# Arduino2.net
KiCad netlist of a schematic drawn in EAGLE
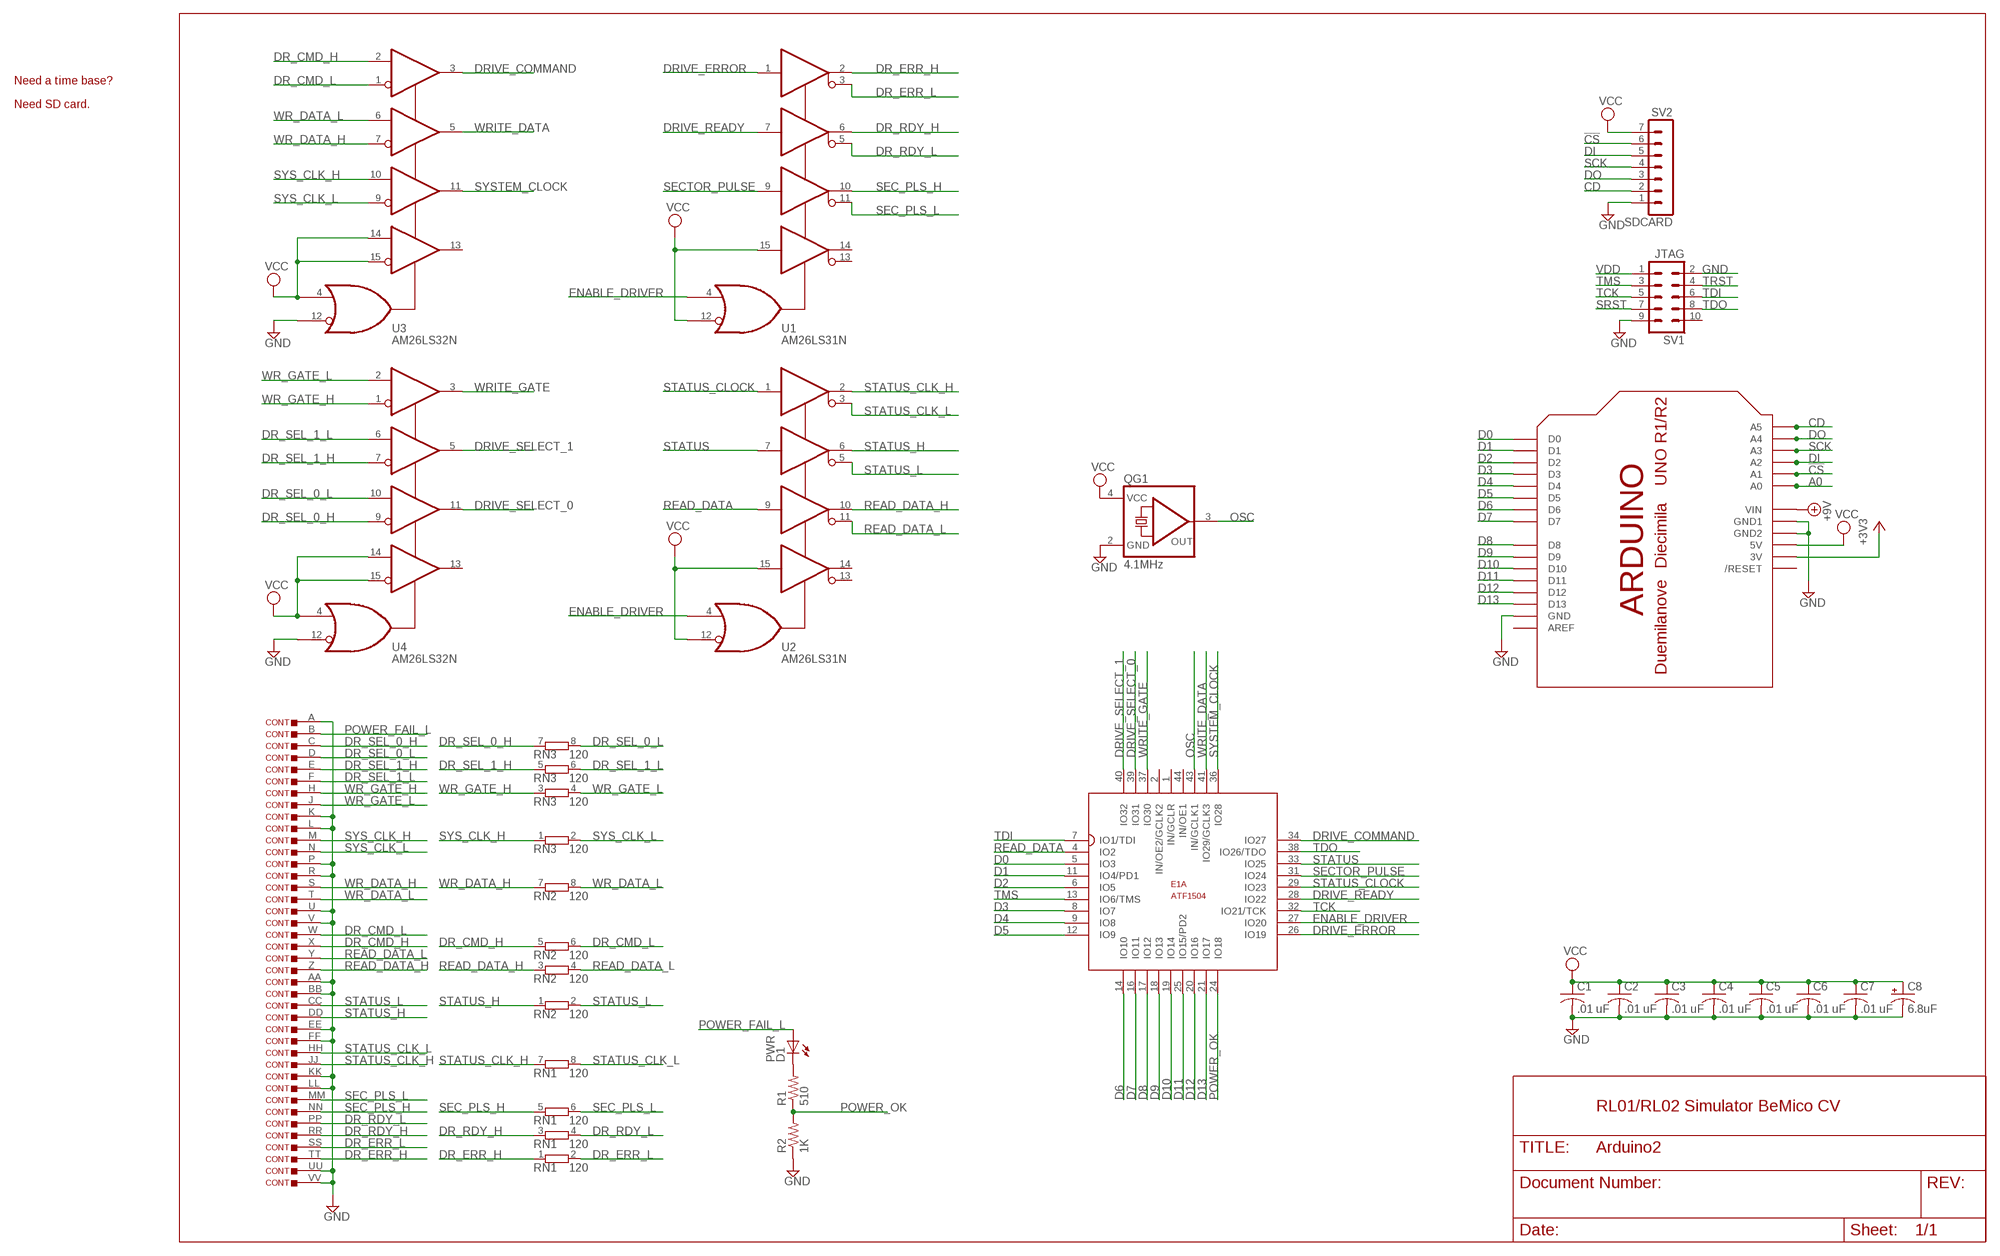
[diagram p0: schematic, sheet 1]

(export (version "E")
  (design (tool "Eeschema 10.0.6"))
  (components
    (comp (ref "C1")
      (value ".01 uF")
      (footprint "eagle-import:C050-025X075")
      (libsource (lib "eagle-import") (part "C-US050-025X075"))
    )
    (comp (ref "C2")
      (value ".01 uF")
      (footprint "eagle-import:C050-025X075")
      (libsource (lib "eagle-import") (part "C-US050-025X075"))
    )
    (comp (ref "C3")
      (value ".01 uF")
      (footprint "eagle-import:C050-025X075")
      (libsource (lib "eagle-import") (part "C-US050-025X075"))
    )
    (comp (ref "C4")
      (value ".01 uF")
      (footprint "eagle-import:C050-025X075")
      (libsource (lib "eagle-import") (part "C-US050-025X075"))
    )
    (comp (ref "C5")
      (value ".01 uF")
      (footprint "eagle-import:C050-025X075")
      (libsource (lib "eagle-import") (part "C-US050-025X075"))
    )
    (comp (ref "C6")
      (value ".01 uF")
      (footprint "eagle-import:C050-025X075")
      (libsource (lib "eagle-import") (part "C-US050-025X075"))
    )
    (comp (ref "C7")
      (value ".01 uF")
      (footprint "eagle-import:C050-025X075")
      (libsource (lib "eagle-import") (part "C-US050-025X075"))
    )
    (comp (ref "C8")
      (value "6.8uF")
      (footprint "eagle-import:E5-5")
      (libsource (lib "eagle-import") (part "CPOL-USE5-5"))
    )
    (comp (ref "CONT")
      (value "DEC40PINSV")
      (footprint "eagle-import:DEC40PINV")
      (libsource (lib "eagle-import") (part "DEC40PINSV"))
    )
    (comp (ref "D1")
      (value "PWR")
      (footprint "eagle-import:LED5MM")
      (libsource (lib "eagle-import") (part "LED5MM"))
    )
    (comp (ref "E1")
      (value "ATF1504")
      (footprint "eagle-import:3M44")
      (libsource (lib "eagle-import") (part "ATF150X44"))
    )
    (comp (ref "QG1")
      (value "4.1MHz")
      (footprint "eagle-import:DIL08-4")
      (fields (field (name "MPN") "SG531P16MHZ"))
      (libsource (lib "eagle-import") (part "SG531"))
    )
    (comp (ref "R1")
      (value "510")
      (footprint "eagle-import:0207_10")
      (libsource (lib "eagle-import") (part "R-US_0207/10"))
    )
    (comp (ref "R2")
      (value "1K")
      (footprint "eagle-import:0207_10")
      (libsource (lib "eagle-import") (part "R-US_0207/10"))
    )
    (comp (ref "RN1")
      (value "120")
      (footprint "eagle-import:SIL8")
      (libsource (lib "eagle-import") (part "E4RP"))
    )
    (comp (ref "RN2")
      (value "120")
      (footprint "eagle-import:SIL8")
      (libsource (lib "eagle-import") (part "E4RP"))
    )
    (comp (ref "RN3")
      (value "120")
      (footprint "eagle-import:SIL8")
      (libsource (lib "eagle-import") (part "E4RP"))
    )
    (comp (ref "SV1")
      (value "JTAG")
      (footprint "eagle-import:ML10")
      (libsource (lib "eagle-import") (part "ML10"))
    )
    (comp (ref "SV2")
      (value "SDCARD")
      (footprint "eagle-import:MA07-1")
      (libsource (lib "eagle-import") (part "MA07-1"))
    )
    (comp (ref "U$3")
      (value "ARDUINODUE")
      (footprint "eagle-import:ARDUINO_DUE_SHIELD")
      (libsource (lib "eagle-import") (part "ARDUINODUE"))
    )
    (comp (ref "U1")
      (value "AM26LS31N")
      (footprint "eagle-import:DIL16")
      (libsource (lib "eagle-import") (part "AM26LS31N"))
    )
    (comp (ref "U2")
      (value "AM26LS31N")
      (footprint "eagle-import:DIL16")
      (libsource (lib "eagle-import") (part "AM26LS31N"))
    )
    (comp (ref "U3")
      (value "AM26LS32N")
      (footprint "eagle-import:DIL16")
      (libsource (lib "eagle-import") (part "AM26LS32N"))
    )
    (comp (ref "U4")
      (value "AM26LS32N")
      (footprint "eagle-import:DIL16")
      (libsource (lib "eagle-import") (part "AM26LS32N"))
    )
  )
  (nets
    (net (code "1") (name "+3V3") (class "Default")
      (node (ref "U$3") (pin "3V3") (pinfunction "3V_3V3") (pintype "power_in"))
    )
    (net (code "2") (name "+9V") (class "Default")
      (node (ref "U$3") (pin "VIN") (pinfunction "VIN_VIN") (pintype "power_in"))
    )
    (net (code "3") (name "/A0") (class "Default")
      (node (ref "U$3") (pin "A0") (pinfunction "A0_A0") (pintype "bidirectional"))
    )
    (net (code "4") (name "/CD") (class "Default")
      (node (ref "SV2") (pin "2") (pinfunction "2_2") (pintype "passive"))
      (node (ref "U$3") (pin "A5") (pinfunction "A5_A5") (pintype "bidirectional"))
    )
    (net (code "5") (name "/D0") (class "Default")
      (node (ref "E1") (pin "5") (pinfunction "IO3_5") (pintype "bidirectional"))
      (node (ref "U$3") (pin "0") (pinfunction "D0_0") (pintype "bidirectional"))
    )
    (net (code "6") (name "/D1") (class "Default")
      (node (ref "E1") (pin "11") (pinfunction "IO4/PD1_11") (pintype "bidirectional"))
      (node (ref "U$3") (pin "1") (pinfunction "D1_1") (pintype "bidirectional"))
    )
    (net (code "7") (name "/D2") (class "Default")
      (node (ref "E1") (pin "6") (pinfunction "IO5_6") (pintype "bidirectional"))
      (node (ref "U$3") (pin "2") (pinfunction "D2_2") (pintype "bidirectional"))
    )
    (net (code "8") (name "/D3") (class "Default")
      (node (ref "E1") (pin "8") (pinfunction "IO7_8") (pintype "bidirectional"))
      (node (ref "U$3") (pin "3") (pinfunction "D3_3") (pintype "bidirectional"))
    )
    (net (code "9") (name "/D4") (class "Default")
      (node (ref "E1") (pin "9") (pinfunction "IO8_9") (pintype "bidirectional"))
      (node (ref "U$3") (pin "4") (pinfunction "D4_4") (pintype "bidirectional"))
    )
    (net (code "10") (name "/D5") (class "Default")
      (node (ref "E1") (pin "12") (pinfunction "IO9_12") (pintype "bidirectional"))
      (node (ref "U$3") (pin "5") (pinfunction "D5_5") (pintype "bidirectional"))
    )
    (net (code "11") (name "/D6") (class "Default")
      (node (ref "E1") (pin "14") (pinfunction "IO10_14") (pintype "bidirectional"))
      (node (ref "U$3") (pin "6") (pinfunction "D6_6") (pintype "bidirectional"))
    )
    (net (code "12") (name "/D7") (class "Default")
      (node (ref "E1") (pin "16") (pinfunction "IO11_16") (pintype "bidirectional"))
      (node (ref "U$3") (pin "7") (pinfunction "D7_7") (pintype "bidirectional"))
    )
    (net (code "13") (name "/D8") (class "Default")
      (node (ref "E1") (pin "17") (pinfunction "IO12_17") (pintype "bidirectional"))
      (node (ref "U$3") (pin "8") (pinfunction "D8_8") (pintype "bidirectional"))
    )
    (net (code "14") (name "/D9") (class "Default")
      (node (ref "E1") (pin "18") (pinfunction "IO13_18") (pintype "bidirectional"))
      (node (ref "U$3") (pin "9") (pinfunction "D9_9") (pintype "bidirectional"))
    )
    (net (code "15") (name "/D10") (class "Default")
      (node (ref "E1") (pin "19") (pinfunction "IO14_19") (pintype "bidirectional"))
      (node (ref "U$3") (pin "10") (pinfunction "D10_10") (pintype "bidirectional"))
    )
    (net (code "16") (name "/D11") (class "Default")
      (node (ref "E1") (pin "25") (pinfunction "IO15/PD2_25") (pintype "bidirectional"))
      (node (ref "U$3") (pin "11") (pinfunction "D11_11") (pintype "bidirectional"))
    )
    (net (code "17") (name "/D12") (class "Default")
      (node (ref "E1") (pin "20") (pinfunction "IO16_20") (pintype "bidirectional"))
      (node (ref "U$3") (pin "12") (pinfunction "D12_12") (pintype "bidirectional"))
    )
    (net (code "18") (name "/D13") (class "Default")
      (node (ref "E1") (pin "21") (pinfunction "IO17_21") (pintype "bidirectional"))
      (node (ref "U$3") (pin "13") (pinfunction "D13_13") (pintype "bidirectional"))
    )
    (net (code "19") (name "/DI") (class "Default")
      (node (ref "SV2") (pin "5") (pinfunction "5_5") (pintype "passive"))
      (node (ref "U$3") (pin "A2") (pinfunction "A2_A2") (pintype "bidirectional"))
    )
    (net (code "20") (name "/DO") (class "Default")
      (node (ref "SV2") (pin "3") (pinfunction "3_3") (pintype "passive"))
      (node (ref "U$3") (pin "A4") (pinfunction "A4_A4") (pintype "bidirectional"))
    )
    (net (code "21") (name "/DRIVE_COMMAND") (class "Default")
      (node (ref "E1") (pin "34") (pinfunction "IO27_34") (pintype "bidirectional"))
      (node (ref "U3") (pin "3") (pinfunction "Y1_3") (pintype "output"))
    )
    (net (code "22") (name "/DRIVE_ERROR") (class "Default")
      (node (ref "E1") (pin "26") (pinfunction "IO19_26") (pintype "bidirectional"))
      (node (ref "U1") (pin "1") (pinfunction "A1_1") (pintype "input"))
    )
    (net (code "23") (name "/DRIVE_READY") (class "Default")
      (node (ref "E1") (pin "28") (pinfunction "IO22_28") (pintype "bidirectional"))
      (node (ref "U1") (pin "7") (pinfunction "A2_7") (pintype "input"))
    )
    (net (code "24") (name "/DRIVE_SELECT_0") (class "Default")
      (node (ref "E1") (pin "39") (pinfunction "IO31_39") (pintype "bidirectional"))
      (node (ref "U4") (pin "11") (pinfunction "Y3_11") (pintype "output"))
    )
    (net (code "25") (name "/DRIVE_SELECT_1") (class "Default")
      (node (ref "E1") (pin "40") (pinfunction "IO32_40") (pintype "bidirectional"))
      (node (ref "U4") (pin "5") (pinfunction "Y2_5") (pintype "output"))
    )
    (net (code "26") (name "/DR_CMD_H") (class "Default")
      (node (ref "CONT") (pin "X") (pinfunction "P$2_X") (pintype "passive"))
      (node (ref "RN2") (pin "5") (pinfunction "1_5") (pintype "passive"))
      (node (ref "U3") (pin "2") (pinfunction "P1_2") (pintype "input"))
    )
    (net (code "27") (name "/DR_CMD_L") (class "Default")
      (node (ref "CONT") (pin "W") (pinfunction "P$2_W") (pintype "passive"))
      (node (ref "RN2") (pin "6") (pinfunction "2_6") (pintype "passive"))
      (node (ref "U3") (pin "1") (pinfunction "N1_1") (pintype "input"))
    )
    (net (code "28") (name "/DR_ERR_H") (class "Default")
      (node (ref "CONT") (pin "TT") (pinfunction "P$2_TT") (pintype "passive"))
      (node (ref "RN1") (pin "1") (pinfunction "1_1") (pintype "passive"))
      (node (ref "U1") (pin "2") (pinfunction "Y1_2") (pintype "output"))
    )
    (net (code "29") (name "/DR_ERR_L") (class "Default")
      (node (ref "CONT") (pin "SS") (pinfunction "P$2_SS") (pintype "passive"))
      (node (ref "RN1") (pin "2") (pinfunction "2_2") (pintype "passive"))
      (node (ref "U1") (pin "3") (pinfunction "Z1_3") (pintype "output"))
    )
    (net (code "30") (name "/DR_RDY_H") (class "Default")
      (node (ref "CONT") (pin "RR") (pinfunction "P$2_RR") (pintype "passive"))
      (node (ref "RN1") (pin "3") (pinfunction "1_3") (pintype "passive"))
      (node (ref "U1") (pin "6") (pinfunction "Y2_6") (pintype "output"))
    )
    (net (code "31") (name "/DR_RDY_L") (class "Default")
      (node (ref "CONT") (pin "PP") (pinfunction "P$2_PP") (pintype "passive"))
      (node (ref "RN1") (pin "4") (pinfunction "2_4") (pintype "passive"))
      (node (ref "U1") (pin "5") (pinfunction "Z2_5") (pintype "output"))
    )
    (net (code "32") (name "/DR_SEL_0_H") (class "Default")
      (node (ref "CONT") (pin "C") (pinfunction "P$2_C") (pintype "passive"))
      (node (ref "RN3") (pin "7") (pinfunction "1_7") (pintype "passive"))
      (node (ref "U4") (pin "9") (pinfunction "N3_9") (pintype "input"))
    )
    (net (code "33") (name "/DR_SEL_0_L") (class "Default")
      (node (ref "CONT") (pin "D") (pinfunction "P$2_D") (pintype "passive"))
      (node (ref "RN3") (pin "8") (pinfunction "2_8") (pintype "passive"))
      (node (ref "U4") (pin "10") (pinfunction "P3_10") (pintype "input"))
    )
    (net (code "34") (name "/DR_SEL_1_H") (class "Default")
      (node (ref "CONT") (pin "E") (pinfunction "P$2_E") (pintype "passive"))
      (node (ref "RN3") (pin "5") (pinfunction "1_5") (pintype "passive"))
      (node (ref "U4") (pin "7") (pinfunction "N2_7") (pintype "input"))
    )
    (net (code "35") (name "/DR_SEL_1_L") (class "Default")
      (node (ref "CONT") (pin "F") (pinfunction "P$2_F") (pintype "passive"))
      (node (ref "RN3") (pin "6") (pinfunction "2_6") (pintype "passive"))
      (node (ref "U4") (pin "6") (pinfunction "P2_6") (pintype "input"))
    )
    (net (code "36") (name "/ENABLE_DRIVER") (class "Default")
      (node (ref "E1") (pin "27") (pinfunction "IO20_27") (pintype "bidirectional"))
      (node (ref "U1") (pin "4") (pinfunction "G_4") (pintype "input"))
      (node (ref "U2") (pin "4") (pinfunction "G_4") (pintype "input"))
    )
    (net (code "37") (name "/OSC") (class "Default")
      (node (ref "E1") (pin "43") (pinfunction "IN/GCLK1_43") (pintype "input"))
      (node (ref "QG1") (pin "3") (pinfunction "OUT_3") (pintype "output"))
    )
    (net (code "38") (name "/POWER_FAIL_L") (class "Default")
      (node (ref "CONT") (pin "B") (pinfunction "P$2_B") (pintype "passive"))
      (node (ref "D1") (pin "A") (pinfunction "A_A") (pintype "passive"))
    )
    (net (code "39") (name "/POWER_OK") (class "Default")
      (node (ref "E1") (pin "24") (pinfunction "IO18_24") (pintype "bidirectional"))
      (node (ref "R1") (pin "1") (pinfunction "1_1") (pintype "passive"))
      (node (ref "R2") (pin "2") (pinfunction "2_2") (pintype "passive"))
    )
    (net (code "40") (name "/READ_DATA") (class "Default")
      (node (ref "E1") (pin "4") (pinfunction "IO2_4") (pintype "bidirectional"))
      (node (ref "U2") (pin "9") (pinfunction "A3_9") (pintype "input"))
    )
    (net (code "41") (name "/READ_DATA_H") (class "Default")
      (node (ref "CONT") (pin "Z") (pinfunction "P$2_Z") (pintype "passive"))
      (node (ref "RN2") (pin "3") (pinfunction "1_3") (pintype "passive"))
      (node (ref "U2") (pin "10") (pinfunction "Y3_10") (pintype "output"))
    )
    (net (code "42") (name "/READ_DATA_L") (class "Default")
      (node (ref "CONT") (pin "Y") (pinfunction "P$2_Y") (pintype "passive"))
      (node (ref "RN2") (pin "4") (pinfunction "2_4") (pintype "passive"))
      (node (ref "U2") (pin "11") (pinfunction "Z3_11") (pintype "output"))
    )
    (net (code "43") (name "/SCK") (class "Default")
      (node (ref "SV2") (pin "4") (pinfunction "4_4") (pintype "passive"))
      (node (ref "U$3") (pin "A3") (pinfunction "A3_A3") (pintype "bidirectional"))
    )
    (net (code "44") (name "/SECTOR_PULSE") (class "Default")
      (node (ref "E1") (pin "31") (pinfunction "IO24_31") (pintype "bidirectional"))
      (node (ref "U1") (pin "9") (pinfunction "A3_9") (pintype "input"))
    )
    (net (code "45") (name "/SEC_PLS_H") (class "Default")
      (node (ref "CONT") (pin "NN") (pinfunction "P$2_NN") (pintype "passive"))
      (node (ref "RN1") (pin "5") (pinfunction "1_5") (pintype "passive"))
      (node (ref "U1") (pin "10") (pinfunction "Y3_10") (pintype "output"))
    )
    (net (code "46") (name "/SEC_PLS_L") (class "Default")
      (node (ref "CONT") (pin "MM") (pinfunction "P$2_MM") (pintype "passive"))
      (node (ref "RN1") (pin "6") (pinfunction "2_6") (pintype "passive"))
      (node (ref "U1") (pin "11") (pinfunction "Z3_11") (pintype "output"))
    )
    (net (code "47") (name "/SRST") (class "Default")
      (node (ref "SV1") (pin "7") (pinfunction "7_7") (pintype "passive"))
    )
    (net (code "48") (name "/STATUS") (class "Default")
      (node (ref "E1") (pin "33") (pinfunction "IO25_33") (pintype "bidirectional"))
      (node (ref "U2") (pin "7") (pinfunction "A2_7") (pintype "input"))
    )
    (net (code "49") (name "/STATUS_CLK_H") (class "Default")
      (node (ref "CONT") (pin "JJ") (pinfunction "P$2_JJ") (pintype "passive"))
      (node (ref "RN1") (pin "7") (pinfunction "1_7") (pintype "passive"))
      (node (ref "U2") (pin "2") (pinfunction "Y1_2") (pintype "output"))
    )
    (net (code "50") (name "/STATUS_CLK_L") (class "Default")
      (node (ref "CONT") (pin "HH") (pinfunction "P$2_HH") (pintype "passive"))
      (node (ref "RN1") (pin "8") (pinfunction "2_8") (pintype "passive"))
      (node (ref "U2") (pin "3") (pinfunction "Z1_3") (pintype "output"))
    )
    (net (code "51") (name "/STATUS_CLOCK") (class "Default")
      (node (ref "E1") (pin "29") (pinfunction "IO23_29") (pintype "bidirectional"))
      (node (ref "U2") (pin "1") (pinfunction "A1_1") (pintype "input"))
    )
    (net (code "52") (name "/STATUS_H") (class "Default")
      (node (ref "CONT") (pin "DD") (pinfunction "P$2_DD") (pintype "passive"))
      (node (ref "RN2") (pin "1") (pinfunction "1_1") (pintype "passive"))
      (node (ref "U2") (pin "6") (pinfunction "Y2_6") (pintype "output"))
    )
    (net (code "53") (name "/STATUS_L") (class "Default")
      (node (ref "CONT") (pin "CC") (pinfunction "P$2_CC") (pintype "passive"))
      (node (ref "RN2") (pin "2") (pinfunction "2_2") (pintype "passive"))
      (node (ref "U2") (pin "5") (pinfunction "Z2_5") (pintype "output"))
    )
    (net (code "54") (name "/SYSTEM_CLOCK") (class "Default")
      (node (ref "E1") (pin "36") (pinfunction "IO28_36") (pintype "bidirectional"))
      (node (ref "U3") (pin "11") (pinfunction "Y3_11") (pintype "output"))
    )
    (net (code "55") (name "/SYS_CLK_H") (class "Default")
      (node (ref "CONT") (pin "M") (pinfunction "P$2_M") (pintype "passive"))
      (node (ref "RN3") (pin "1") (pinfunction "1_1") (pintype "passive"))
      (node (ref "U3") (pin "10") (pinfunction "P3_10") (pintype "input"))
    )
    (net (code "56") (name "/SYS_CLK_L") (class "Default")
      (node (ref "CONT") (pin "N") (pinfunction "P$2_N") (pintype "passive"))
      (node (ref "RN3") (pin "2") (pinfunction "2_2") (pintype "passive"))
      (node (ref "U3") (pin "9") (pinfunction "N3_9") (pintype "input"))
    )
    (net (code "57") (name "/TCK") (class "Default")
      (node (ref "E1") (pin "32") (pinfunction "IO21/TCK_32") (pintype "bidirectional"))
      (node (ref "SV1") (pin "5") (pinfunction "5_5") (pintype "passive"))
    )
    (net (code "58") (name "/TDI") (class "Default")
      (node (ref "E1") (pin "7") (pinfunction "IO1/TDI_7") (pintype "bidirectional"))
      (node (ref "SV1") (pin "6") (pinfunction "6_6") (pintype "passive"))
    )
    (net (code "59") (name "/TDO") (class "Default")
      (node (ref "E1") (pin "38") (pinfunction "IO26/TDO_38") (pintype "bidirectional"))
      (node (ref "SV1") (pin "8") (pinfunction "8_8") (pintype "passive"))
    )
    (net (code "60") (name "/TMS") (class "Default")
      (node (ref "E1") (pin "13") (pinfunction "IO6/TMS_13") (pintype "bidirectional"))
      (node (ref "SV1") (pin "3") (pinfunction "3_3") (pintype "passive"))
    )
    (net (code "61") (name "/TRST") (class "Default")
      (node (ref "SV1") (pin "4") (pinfunction "4_4") (pintype "passive"))
    )
    (net (code "62") (name "/VDD") (class "Default")
      (node (ref "SV1") (pin "1") (pinfunction "1_1") (pintype "passive"))
    )
    (net (code "63") (name "/WRITE_DATA") (class "Default")
      (node (ref "E1") (pin "41") (pinfunction "IO29/GCLK3_41") (pintype "bidirectional"))
      (node (ref "U3") (pin "5") (pinfunction "Y2_5") (pintype "output"))
    )
    (net (code "64") (name "/WRITE_GATE") (class "Default")
      (node (ref "E1") (pin "37") (pinfunction "IO30_37") (pintype "bidirectional"))
      (node (ref "U4") (pin "3") (pinfunction "Y1_3") (pintype "output"))
    )
    (net (code "65") (name "/WR_DATA_H") (class "Default")
      (node (ref "CONT") (pin "S") (pinfunction "P$2_S") (pintype "passive"))
      (node (ref "RN2") (pin "7") (pinfunction "1_7") (pintype "passive"))
      (node (ref "U3") (pin "7") (pinfunction "N2_7") (pintype "input"))
    )
    (net (code "66") (name "/WR_DATA_L") (class "Default")
      (node (ref "CONT") (pin "T") (pinfunction "P$2_T") (pintype "passive"))
      (node (ref "RN2") (pin "8") (pinfunction "2_8") (pintype "passive"))
      (node (ref "U3") (pin "6") (pinfunction "P2_6") (pintype "input"))
    )
    (net (code "67") (name "/WR_GATE_H") (class "Default")
      (node (ref "CONT") (pin "H") (pinfunction "P$2_H") (pintype "passive"))
      (node (ref "RN3") (pin "3") (pinfunction "1_3") (pintype "passive"))
      (node (ref "U4") (pin "1") (pinfunction "N1_1") (pintype "input"))
    )
    (net (code "68") (name "/WR_GATE_L") (class "Default")
      (node (ref "CONT") (pin "J") (pinfunction "P$2_J") (pintype "passive"))
      (node (ref "RN3") (pin "4") (pinfunction "2_4") (pintype "passive"))
      (node (ref "U4") (pin "2") (pinfunction "P1_2") (pintype "input"))
    )
    (net (code "69") (name "/~{CS}") (class "Default")
      (node (ref "SV2") (pin "6") (pinfunction "6_6") (pintype "passive"))
      (node (ref "U$3") (pin "A1") (pinfunction "A1_A1") (pintype "bidirectional"))
    )
    (net (code "70") (name "GND") (class "Default")
      (node (ref "C1") (pin "2") (pinfunction "2_2") (pintype "passive"))
      (node (ref "C2") (pin "2") (pinfunction "2_2") (pintype "passive"))
      (node (ref "C3") (pin "2") (pinfunction "2_2") (pintype "passive"))
      (node (ref "C4") (pin "2") (pinfunction "2_2") (pintype "passive"))
      (node (ref "C5") (pin "2") (pinfunction "2_2") (pintype "passive"))
      (node (ref "C6") (pin "2") (pinfunction "2_2") (pintype "passive"))
      (node (ref "C7") (pin "2") (pinfunction "2_2") (pintype "passive"))
      (node (ref "C8") (pin "-") (pinfunction "-_-") (pintype "passive"))
      (node (ref "CONT") (pin "A") (pinfunction "P$2_A") (pintype "passive"))
      (node (ref "CONT") (pin "AA") (pinfunction "P$2_AA") (pintype "passive"))
      (node (ref "CONT") (pin "BB") (pinfunction "P$2_BB") (pintype "passive"))
      (node (ref "CONT") (pin "EE") (pinfunction "P$2_EE") (pintype "passive"))
      (node (ref "CONT") (pin "FF") (pinfunction "P$2_FF") (pintype "passive"))
      (node (ref "CONT") (pin "K") (pinfunction "P$2_K") (pintype "passive"))
      (node (ref "CONT") (pin "KK") (pinfunction "P$2_KK") (pintype "passive"))
      (node (ref "CONT") (pin "L") (pinfunction "P$2_L") (pintype "passive"))
      (node (ref "CONT") (pin "LL") (pinfunction "P$2_LL") (pintype "passive"))
      (node (ref "CONT") (pin "P") (pinfunction "P$2_P") (pintype "passive"))
      (node (ref "CONT") (pin "R") (pinfunction "P$2_R") (pintype "passive"))
      (node (ref "CONT") (pin "U") (pinfunction "P$2_U") (pintype "passive"))
      (node (ref "CONT") (pin "UU") (pinfunction "P$2_UU") (pintype "passive"))
      (node (ref "CONT") (pin "V") (pinfunction "P$2_V") (pintype "passive"))
      (node (ref "CONT") (pin "VV") (pinfunction "P$2_VV") (pintype "passive"))
      (node (ref "QG1") (pin "2") (pinfunction "GND_2") (pintype "power_in"))
      (node (ref "R2") (pin "1") (pinfunction "1_1") (pintype "passive"))
      (node (ref "SV1") (pin "2") (pinfunction "2_2") (pintype "passive"))
      (node (ref "SV1") (pin "9") (pinfunction "9_9") (pintype "passive"))
      (node (ref "SV2") (pin "1") (pinfunction "1_1") (pintype "passive"))
      (node (ref "U$3") (pin "GND") (pinfunction "GND_GND") (pintype "power_in"))
      (node (ref "U$3") (pin "GND_1") (pinfunction "GND1_GND_1") (pintype "power_in"))
      (node (ref "U$3") (pin "GND_2") (pinfunction "GND2_GND_2") (pintype "power_in"))
      (node (ref "U3") (pin "12") (pinfunction "~{G}_12") (pintype "input"))
      (node (ref "U4") (pin "12") (pinfunction "~{G}_12") (pintype "input"))
    )
    (net (code "71") (name "Net-(D1-C)") (class "Default")
      (node (ref "D1") (pin "K") (pinfunction "C_K") (pintype "passive"))
      (node (ref "R1") (pin "2") (pinfunction "2_2") (pintype "passive"))
    )
    (net (code "72") (name "VCC") (class "Default")
      (node (ref "C1") (pin "1") (pinfunction "1_1") (pintype "passive"))
      (node (ref "C2") (pin "1") (pinfunction "1_1") (pintype "passive"))
      (node (ref "C3") (pin "1") (pinfunction "1_1") (pintype "passive"))
      (node (ref "C4") (pin "1") (pinfunction "1_1") (pintype "passive"))
      (node (ref "C5") (pin "1") (pinfunction "1_1") (pintype "passive"))
      (node (ref "C6") (pin "1") (pinfunction "1_1") (pintype "passive"))
      (node (ref "C7") (pin "1") (pinfunction "1_1") (pintype "passive"))
      (node (ref "C8") (pin "+") (pinfunction "+_+") (pintype "passive"))
      (node (ref "QG1") (pin "4") (pinfunction "VCC_4") (pintype "power_in"))
      (node (ref "SV2") (pin "7") (pinfunction "7_7") (pintype "passive"))
      (node (ref "U$3") (pin "5V0") (pinfunction "5V_5V0") (pintype "power_in"))
      (node (ref "U1") (pin "12") (pinfunction "~{G}_12") (pintype "input"))
      (node (ref "U1") (pin "15") (pinfunction "A4_15") (pintype "input"))
      (node (ref "U2") (pin "12") (pinfunction "~{G}_12") (pintype "input"))
      (node (ref "U2") (pin "15") (pinfunction "A4_15") (pintype "input"))
      (node (ref "U3") (pin "14") (pinfunction "P4_14") (pintype "input"))
      (node (ref "U3") (pin "15") (pinfunction "N4_15") (pintype "input"))
      (node (ref "U3") (pin "4") (pinfunction "G_4") (pintype "input"))
      (node (ref "U4") (pin "14") (pinfunction "P4_14") (pintype "input"))
      (node (ref "U4") (pin "15") (pinfunction "N4_15") (pintype "input"))
      (node (ref "U4") (pin "4") (pinfunction "G_4") (pintype "input"))
    )
    (net (code "73") (name "unconnected-(E1A-IN{slash}GCLR-Pad1)") (class "Default")
      (node (ref "E1") (pin "1") (pinfunction "IN/GCLR_1") (pintype "input"))
    )
    (net (code "74") (name "unconnected-(E1A-IN{slash}OE1-Pad44)") (class "Default")
      (node (ref "E1") (pin "44") (pinfunction "IN/OE1_44") (pintype "input"))
    )
    (net (code "75") (name "unconnected-(E1A-IN{slash}OE2{slash}GCLK2-Pad2)") (class "Default")
      (node (ref "E1") (pin "2") (pinfunction "IN/OE2/GCLK2_2") (pintype "input"))
    )
    (net (code "76") (name "unconnected-(SV1-Pad10)") (class "Default")
      (node (ref "SV1") (pin "10") (pinfunction "10_10") (pintype "passive"))
    )
    (net (code "77") (name "unconnected-(U$3-PadAREF)") (class "Default")
      (node (ref "U$3") (pin "AREF") (pinfunction "AREF_AREF") (pintype "bidirectional"))
    )
    (net (code "78") (name "unconnected-(U$3-{slash}RESET-PadRESET)") (class "Default")
      (node (ref "U$3") (pin "RESET") (pinfunction "/RESET_RESET") (pintype "bidirectional"))
    )
    (net (code "79") (name "unconnected-(U1A-Y4-Pad14)") (class "Default")
      (node (ref "U1") (pin "14") (pinfunction "Y4_14") (pintype "output"))
    )
    (net (code "80") (name "unconnected-(U1A-Z4-Pad13)") (class "Default")
      (node (ref "U1") (pin "13") (pinfunction "Z4_13") (pintype "output"))
    )
    (net (code "81") (name "unconnected-(U2A-Y4-Pad14)") (class "Default")
      (node (ref "U2") (pin "14") (pinfunction "Y4_14") (pintype "output"))
    )
    (net (code "82") (name "unconnected-(U2A-Z4-Pad13)") (class "Default")
      (node (ref "U2") (pin "13") (pinfunction "Z4_13") (pintype "output"))
    )
    (net (code "83") (name "unconnected-(U3A-Y4-Pad13)") (class "Default")
      (node (ref "U3") (pin "13") (pinfunction "Y4_13") (pintype "output"))
    )
    (net (code "84") (name "unconnected-(U4A-Y4-Pad13)") (class "Default")
      (node (ref "U4") (pin "13") (pinfunction "Y4_13") (pintype "output"))
    )
  )
)
